# Power_Dev_revA_1.net
KiCad netlist of a schematic drawn in EAGLE
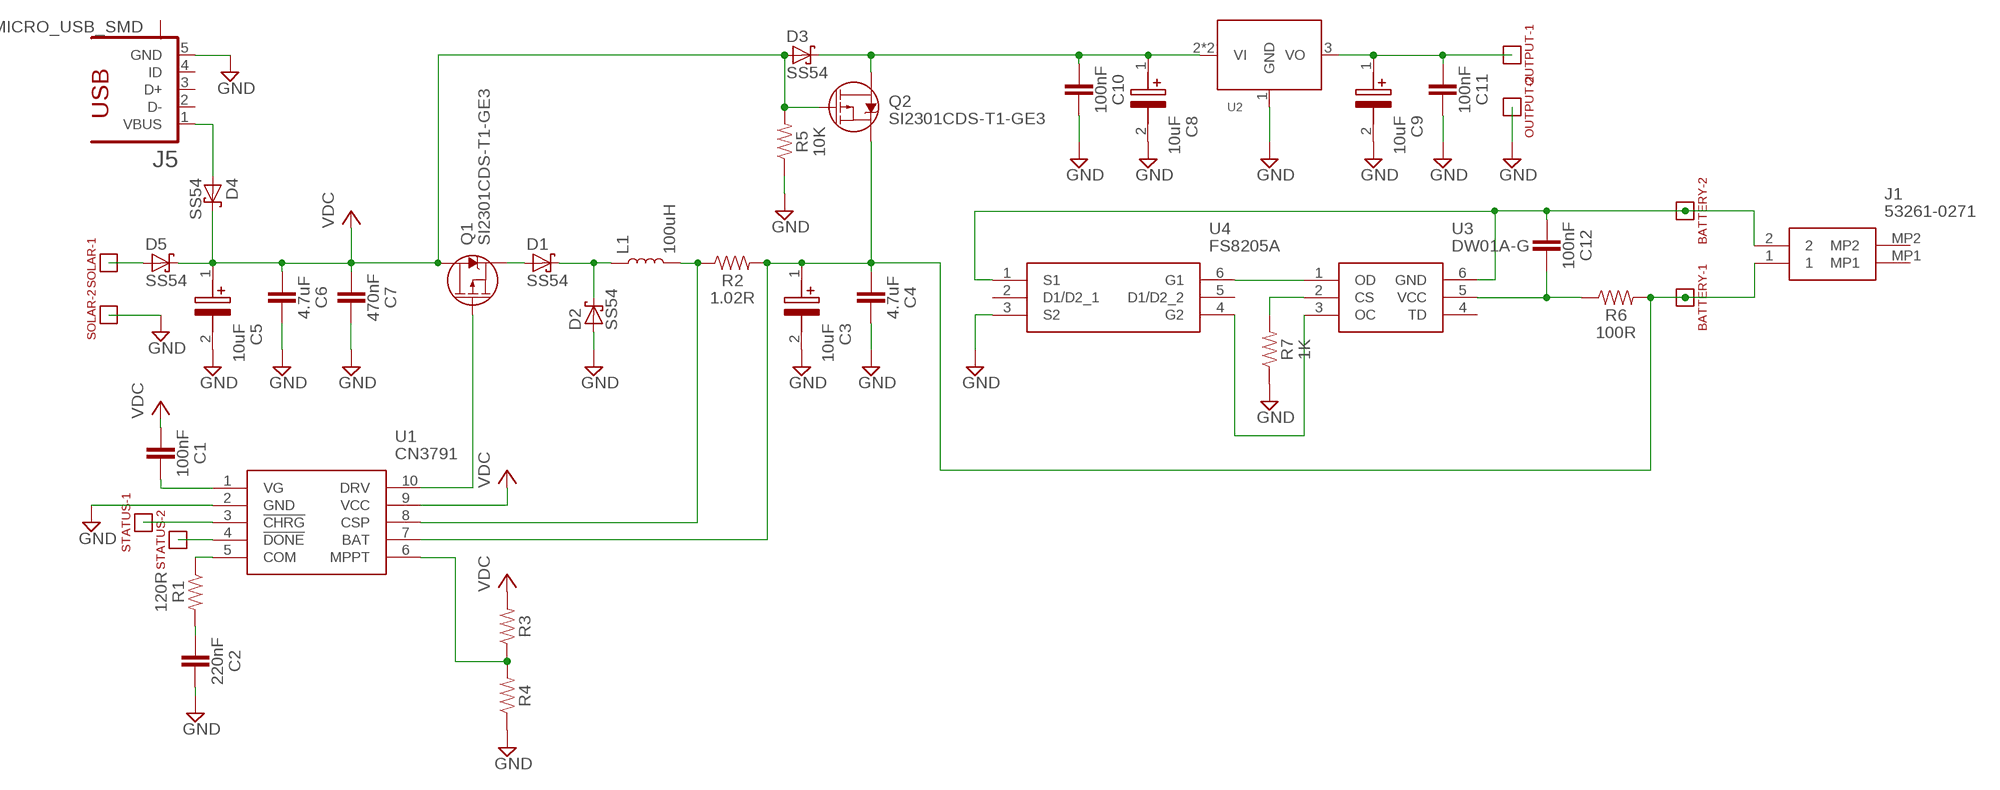
[diagram p0: schematic, sheet 1]

(export (version "E")
  (design (tool "Eeschema 10.0.6"))
  (components
    (comp (ref "BATTERY")
      (value "HEADER_2PIN")
      (footprint "eagle-import:HEADER_2PIN")
      (libsource (lib "eagle-import") (part "HEADER_2PIN"))
    )
    (comp (ref "C1")
      (value "100nF")
      (footprint "eagle-import:0402")
      (libsource (lib "eagle-import") (part "C_0402"))
    )
    (comp (ref "C2")
      (value "220nF")
      (footprint "eagle-import:0603")
      (libsource (lib "eagle-import") (part "C_0603"))
    )
    (comp (ref "C3")
      (value "10uF")
      (footprint "eagle-import:6MM_SMD_ECAP")
      (libsource (lib "eagle-import") (part "6.3MM_SMD_ECAP"))
    )
    (comp (ref "C4")
      (value "4.7uF")
      (footprint "eagle-import:1206")
      (libsource (lib "eagle-import") (part "C_1206"))
    )
    (comp (ref "C5")
      (value "10uF")
      (footprint "eagle-import:6MM_SMD_ECAP")
      (libsource (lib "eagle-import") (part "6.3MM_SMD_ECAP"))
    )
    (comp (ref "C6")
      (value "4.7uF")
      (footprint "eagle-import:1206")
      (libsource (lib "eagle-import") (part "C_1206"))
    )
    (comp (ref "C7")
      (value "470nF")
      (footprint "eagle-import:0805")
      (libsource (lib "eagle-import") (part "C_0805"))
    )
    (comp (ref "C8")
      (value "10uF")
      (footprint "eagle-import:6MM_SMD_ECAP")
      (libsource (lib "eagle-import") (part "6.3MM_SMD_ECAP"))
    )
    (comp (ref "C9")
      (value "10uF")
      (footprint "eagle-import:6MM_SMD_ECAP")
      (libsource (lib "eagle-import") (part "6.3MM_SMD_ECAP"))
    )
    (comp (ref "C10")
      (value "100nF")
      (footprint "eagle-import:0402")
      (libsource (lib "eagle-import") (part "C_0402"))
    )
    (comp (ref "C11")
      (value "100nF")
      (footprint "eagle-import:0402")
      (libsource (lib "eagle-import") (part "C_0402"))
    )
    (comp (ref "C12")
      (value "100nF")
      (footprint "eagle-import:0402")
      (libsource (lib "eagle-import") (part "C_0402"))
    )
    (comp (ref "D1")
      (value "SS54")
      (footprint "eagle-import:SMA(DO-214AC)")
      (libsource (lib "eagle-import") (part "DIODE_SCHOTTKY_SMA"))
    )
    (comp (ref "D2")
      (value "SS54")
      (footprint "eagle-import:SMA(DO-214AC)")
      (libsource (lib "eagle-import") (part "DIODE_SCHOTTKY_SMA"))
    )
    (comp (ref "D3")
      (value "SS54")
      (footprint "eagle-import:SMA(DO-214AC)")
      (libsource (lib "eagle-import") (part "DIODE_SCHOTTKY_SMA"))
    )
    (comp (ref "D4")
      (value "SS54")
      (footprint "eagle-import:SMA(DO-214AC)")
      (libsource (lib "eagle-import") (part "DIODE_SCHOTTKY_SMA"))
    )
    (comp (ref "D5")
      (value "SS54")
      (footprint "eagle-import:SMA(DO-214AC)")
      (libsource (lib "eagle-import") (part "DIODE_SCHOTTKY_SMA"))
    )
    (comp (ref "J1")
      (value "53261-0271")
      (footprint "eagle-import:532610271")
      (fields (field (name "MOUSER_PART_NUMBER") "538-53261-0271"))
      (libsource (lib "eagle-import") (part "53261-0271"))
    )
    (comp (ref "J5")
      (value "MICRO_USB_SMD")
      (footprint "eagle-import:10118192-0002LF")
      (libsource (lib "eagle-import") (part "MICRO_USB_SMD"))
    )
    (comp (ref "L1")
      (value "100uH")
      (footprint "eagle-import:L_SMD,7X7.8MM")
      (libsource (lib "eagle-import") (part "L_SMD,7X7.8MM"))
    )
    (comp (ref "OUTPUT")
      (value "HEADER_2PIN")
      (footprint "eagle-import:HEADER_2PIN")
      (libsource (lib "eagle-import") (part "HEADER_2PIN"))
    )
    (comp (ref "Q1")
      (value "SI2301CDS-T1-GE3")
      (footprint "eagle-import:SOT-23")
      (libsource (lib "eagle-import") (part "MOSFET_P_SOT23"))
    )
    (comp (ref "Q2")
      (value "SI2301CDS-T1-GE3")
      (footprint "eagle-import:SOT-23")
      (libsource (lib "eagle-import") (part "MOSFET_P_SOT23"))
    )
    (comp (ref "R1")
      (value "120R")
      (footprint "eagle-import:0805")
      (libsource (lib "eagle-import") (part "R_0805"))
    )
    (comp (ref "R2")
      (value "1.02R")
      (footprint "eagle-import:1206")
      (libsource (lib "eagle-import") (part "R_1206"))
    )
    (comp (ref "R3")
      (value "RESISTOR_TH")
      (footprint "eagle-import:RESISTOR_TH")
      (libsource (lib "eagle-import") (part "RESISTOR_TH"))
    )
    (comp (ref "R4")
      (value "RESISTOR_TH")
      (footprint "eagle-import:RESISTOR_TH")
      (libsource (lib "eagle-import") (part "RESISTOR_TH"))
    )
    (comp (ref "R5")
      (value "10K")
      (footprint "eagle-import:0402")
      (libsource (lib "eagle-import") (part "R_0402"))
    )
    (comp (ref "R6")
      (value "100R")
      (footprint "eagle-import:0402")
      (libsource (lib "eagle-import") (part "R_0402"))
    )
    (comp (ref "R7")
      (value "1K")
      (footprint "eagle-import:0402")
      (libsource (lib "eagle-import") (part "R_0402"))
    )
    (comp (ref "SOLAR")
      (value "HEADER_2PIN")
      (footprint "eagle-import:HEADER_2PIN")
      (libsource (lib "eagle-import") (part "HEADER_2PIN"))
    )
    (comp (ref "STATUS")
      (value "HEADER_2PIN")
      (footprint "eagle-import:HEADER_2PIN")
      (libsource (lib "eagle-import") (part "HEADER_2PIN"))
    )
    (comp (ref "U1")
      (value "CN3791")
      (footprint "eagle-import:SOP100P600X175-10N")
      (libsource (lib "eagle-import") (part "CN3791"))
    )
    (comp (ref "U2")
      (value "LDO_SOT89")
      (footprint "eagle-import:SOT-89-3")
      (libsource (lib "eagle-import") (part "LDO_SOT89"))
    )
    (comp (ref "U3")
      (value "DW01A-G")
      (footprint "eagle-import:SOT95P280X135-6N")
      (libsource (lib "eagle-import") (part "DW01A-G"))
    )
    (comp (ref "U4")
      (value "FS8205A")
      (footprint "eagle-import:SOT95P280X125-6N")
      (libsource (lib "eagle-import") (part "FS8205A"))
    )
  )
  (nets
    (net (code "1") (name "GND") (class "Default")
      (node (ref "C10") (pin "2") (pinfunction "2_2") (pintype "passive"))
      (node (ref "C11") (pin "2") (pinfunction "2_2") (pintype "passive"))
      (node (ref "C2") (pin "2") (pinfunction "2_2") (pintype "passive"))
      (node (ref "C3") (pin "2") (pinfunction "-_2") (pintype "bidirectional"))
      (node (ref "C4") (pin "2") (pinfunction "2_2") (pintype "passive"))
      (node (ref "C5") (pin "2") (pinfunction "-_2") (pintype "bidirectional"))
      (node (ref "C6") (pin "2") (pinfunction "2_2") (pintype "passive"))
      (node (ref "C7") (pin "2") (pinfunction "2_2") (pintype "passive"))
      (node (ref "C8") (pin "2") (pinfunction "-_2") (pintype "bidirectional"))
      (node (ref "C9") (pin "2") (pinfunction "-_2") (pintype "bidirectional"))
      (node (ref "D2") (pin "2") (pinfunction "A_2") (pintype "passive"))
      (node (ref "J5") (pin "5") (pinfunction "GND_5") (pintype "passive"))
      (node (ref "OUTPUT") (pin "P$2") (pinfunction "P$1_P$2") (pintype "bidirectional"))
      (node (ref "R4") (pin "P$1") (pinfunction "1_P$1") (pintype "passive"))
      (node (ref "R5") (pin "1") (pinfunction "1_1") (pintype "passive"))
      (node (ref "R7") (pin "1") (pinfunction "1_1") (pintype "passive"))
      (node (ref "SOLAR") (pin "P$2") (pinfunction "P$1_P$2") (pintype "bidirectional"))
      (node (ref "U1") (pin "2") (pinfunction "GND_2") (pintype "bidirectional"))
      (node (ref "U2") (pin "1") (pinfunction "GND_1") (pintype "bidirectional"))
      (node (ref "U4") (pin "3") (pinfunction "S2_3") (pintype "bidirectional"))
    )
    (net (code "2") (name "Net-(BATTERYB-P$1)") (class "Default")
      (node (ref "BATTERY") (pin "P$2") (pinfunction "P$1_P$2") (pintype "bidirectional"))
      (node (ref "C12") (pin "1") (pinfunction "1_1") (pintype "passive"))
      (node (ref "J1") (pin "2") (pinfunction "2_2") (pintype "bidirectional"))
      (node (ref "U3") (pin "6") (pinfunction "GND_6") (pintype "bidirectional"))
      (node (ref "U4") (pin "1") (pinfunction "S1_1") (pintype "bidirectional"))
    )
    (net (code "3") (name "Net-(C2-Pad1)") (class "Default")
      (node (ref "C2") (pin "1") (pinfunction "1_1") (pintype "passive"))
      (node (ref "R1") (pin "2") (pinfunction "2_2") (pintype "passive"))
    )
    (net (code "4") (name "Net-(C3-+)") (class "Default")
      (node (ref "BATTERY") (pin "P$1") (pinfunction "P$1_P$1") (pintype "bidirectional"))
      (node (ref "C3") (pin "1") (pinfunction "+_1") (pintype "bidirectional"))
      (node (ref "C4") (pin "1") (pinfunction "1_1") (pintype "passive"))
      (node (ref "J1") (pin "1") (pinfunction "1_1") (pintype "bidirectional"))
      (node (ref "Q2") (pin "3") (pinfunction "S_3") (pintype "bidirectional"))
      (node (ref "R2") (pin "2") (pinfunction "2_2") (pintype "passive"))
      (node (ref "R6") (pin "2") (pinfunction "2_2") (pintype "passive"))
      (node (ref "U1") (pin "7") (pinfunction "BAT_7") (pintype "bidirectional"))
    )
    (net (code "5") (name "Net-(C8-+)") (class "Default")
      (node (ref "C10") (pin "1") (pinfunction "1_1") (pintype "passive"))
      (node (ref "C8") (pin "1") (pinfunction "+_1") (pintype "bidirectional"))
      (node (ref "D3") (pin "1") (pinfunction "C_1") (pintype "passive"))
      (node (ref "Q2") (pin "2") (pinfunction "D_2") (pintype "bidirectional"))
      (node (ref "U2") (pin "2") (pinfunction "VI_2") (pintype "bidirectional"))
      (node (ref "U2") (pin "4") (pinfunction "VI_4") (pintype "bidirectional"))
    )
    (net (code "6") (name "Net-(C9-+)") (class "Default")
      (node (ref "C11") (pin "1") (pinfunction "1_1") (pintype "passive"))
      (node (ref "C9") (pin "1") (pinfunction "+_1") (pintype "bidirectional"))
      (node (ref "OUTPUT") (pin "P$1") (pinfunction "P$1_P$1") (pintype "bidirectional"))
      (node (ref "U2") (pin "3") (pinfunction "VO_3") (pintype "bidirectional"))
    )
    (net (code "7") (name "Net-(D1-A)") (class "Default")
      (node (ref "D1") (pin "2") (pinfunction "A_2") (pintype "passive"))
      (node (ref "Q1") (pin "3") (pinfunction "S_3") (pintype "bidirectional"))
    )
    (net (code "8") (name "Net-(D1-C)") (class "Default")
      (node (ref "D1") (pin "1") (pinfunction "C_1") (pintype "passive"))
      (node (ref "D2") (pin "1") (pinfunction "C_1") (pintype "passive"))
      (node (ref "L1") (pin "P$1") (pinfunction "1_P$1") (pintype "passive"))
    )
    (net (code "9") (name "Net-(D4-A)") (class "Default")
      (node (ref "D4") (pin "2") (pinfunction "A_2") (pintype "passive"))
      (node (ref "J5") (pin "1") (pinfunction "VBUS_1") (pintype "passive"))
    )
    (net (code "10") (name "Net-(D5-A)") (class "Default")
      (node (ref "D5") (pin "2") (pinfunction "A_2") (pintype "passive"))
      (node (ref "SOLAR") (pin "P$1") (pinfunction "P$1_P$1") (pintype "bidirectional"))
    )
    (net (code "11") (name "Net-(L1-2)") (class "Default")
      (node (ref "L1") (pin "P$2") (pinfunction "2_P$2") (pintype "passive"))
      (node (ref "R2") (pin "1") (pinfunction "1_1") (pintype "passive"))
      (node (ref "U1") (pin "8") (pinfunction "CSP_8") (pintype "bidirectional"))
    )
    (net (code "12") (name "Net-(Q1-G)") (class "Default")
      (node (ref "Q1") (pin "1") (pinfunction "G_1") (pintype "bidirectional"))
      (node (ref "U1") (pin "10") (pinfunction "DRV_10") (pintype "bidirectional"))
    )
    (net (code "13") (name "Net-(R3-1)") (class "Default")
      (node (ref "R3") (pin "P$1") (pinfunction "1_P$1") (pintype "passive"))
      (node (ref "R4") (pin "P$2") (pinfunction "2_P$2") (pintype "passive"))
      (node (ref "U1") (pin "6") (pinfunction "MPPT_6") (pintype "bidirectional"))
    )
    (net (code "14") (name "Net-(STATUSB-P$1)") (class "Default")
      (node (ref "STATUS") (pin "P$2") (pinfunction "P$1_P$2") (pintype "bidirectional"))
      (node (ref "U1") (pin "4") (pinfunction "~{DONE}_4") (pintype "bidirectional"))
    )
    (net (code "15") (name "Net-(U1-COM)") (class "Default")
      (node (ref "R1") (pin "1") (pinfunction "1_1") (pintype "passive"))
      (node (ref "U1") (pin "5") (pinfunction "COM_5") (pintype "bidirectional"))
    )
    (net (code "16") (name "Net-(U1-VG)") (class "Default")
      (node (ref "C1") (pin "2") (pinfunction "2_2") (pintype "passive"))
      (node (ref "U1") (pin "1") (pinfunction "VG_1") (pintype "bidirectional"))
    )
    (net (code "17") (name "Net-(U1-~{CHRG})") (class "Default")
      (node (ref "STATUS") (pin "P$1") (pinfunction "P$1_P$1") (pintype "bidirectional"))
      (node (ref "U1") (pin "3") (pinfunction "~{CHRG}_3") (pintype "bidirectional"))
    )
    (net (code "18") (name "Net-(U3-CS)") (class "Default")
      (node (ref "R7") (pin "2") (pinfunction "2_2") (pintype "passive"))
      (node (ref "U3") (pin "2") (pinfunction "CS_2") (pintype "bidirectional"))
    )
    (net (code "19") (name "Net-(U3-OC)") (class "Default")
      (node (ref "U3") (pin "3") (pinfunction "OC_3") (pintype "bidirectional"))
      (node (ref "U4") (pin "4") (pinfunction "G2_4") (pintype "bidirectional"))
    )
    (net (code "20") (name "Net-(U3-OD)") (class "Default")
      (node (ref "U3") (pin "1") (pinfunction "OD_1") (pintype "bidirectional"))
      (node (ref "U4") (pin "6") (pinfunction "G1_6") (pintype "bidirectional"))
    )
    (net (code "21") (name "Net-(U3-VCC)") (class "Default")
      (node (ref "C12") (pin "2") (pinfunction "2_2") (pintype "passive"))
      (node (ref "R6") (pin "1") (pinfunction "1_1") (pintype "passive"))
      (node (ref "U3") (pin "5") (pinfunction "VCC_5") (pintype "bidirectional"))
    )
    (net (code "22") (name "VDC") (class "Default")
      (node (ref "C1") (pin "1") (pinfunction "1_1") (pintype "passive"))
      (node (ref "C5") (pin "1") (pinfunction "+_1") (pintype "bidirectional"))
      (node (ref "C6") (pin "1") (pinfunction "1_1") (pintype "passive"))
      (node (ref "C7") (pin "1") (pinfunction "1_1") (pintype "passive"))
      (node (ref "D3") (pin "2") (pinfunction "A_2") (pintype "passive"))
      (node (ref "D4") (pin "1") (pinfunction "C_1") (pintype "passive"))
      (node (ref "D5") (pin "1") (pinfunction "C_1") (pintype "passive"))
      (node (ref "Q1") (pin "2") (pinfunction "D_2") (pintype "bidirectional"))
      (node (ref "Q2") (pin "1") (pinfunction "G_1") (pintype "bidirectional"))
      (node (ref "R3") (pin "P$2") (pinfunction "2_P$2") (pintype "passive"))
      (node (ref "R5") (pin "2") (pinfunction "2_2") (pintype "passive"))
      (node (ref "U1") (pin "9") (pinfunction "VCC_9") (pintype "bidirectional"))
    )
    (net (code "23") (name "unconnected-(J1-PadMP1)") (class "Default")
      (node (ref "J1") (pin "MP1") (pinfunction "MP1_MP1") (pintype "bidirectional"))
    )
    (net (code "24") (name "unconnected-(J1-PadMP2)") (class "Default")
      (node (ref "J1") (pin "MP2") (pinfunction "MP2_MP2") (pintype "bidirectional"))
    )
    (net (code "25") (name "unconnected-(J5-D+-Pad3)") (class "Default")
      (node (ref "J5") (pin "3") (pinfunction "D+_3") (pintype "passive"))
    )
    (net (code "26") (name "unconnected-(J5-D--Pad2)") (class "Default")
      (node (ref "J5") (pin "2") (pinfunction "D-_2") (pintype "passive"))
    )
    (net (code "27") (name "unconnected-(J5-ID-Pad4)") (class "Default")
      (node (ref "J5") (pin "4") (pinfunction "ID_4") (pintype "passive"))
    )
    (net (code "28") (name "unconnected-(J5-PadS1)") (class "Default")
      (node (ref "J5") (pin "S1") (pinfunction "S1_S1") (pintype "passive"))
    )
    (net (code "29") (name "unconnected-(U3-TD-Pad4)") (class "Default")
      (node (ref "U3") (pin "4") (pinfunction "TD_4") (pintype "bidirectional"))
    )
    (net (code "30") (name "unconnected-(U4-D1{slash}D2_1-Pad2)") (class "Default")
      (node (ref "U4") (pin "2") (pinfunction "D1/D2_1_2") (pintype "bidirectional"))
    )
    (net (code "31") (name "unconnected-(U4-D1{slash}D2_2-Pad5)") (class "Default")
      (node (ref "U4") (pin "5") (pinfunction "D1/D2_2_5") (pintype "bidirectional"))
    )
  )
)
